# Actuators.net
KiCad netlist of a schematic drawn in Altium Designer
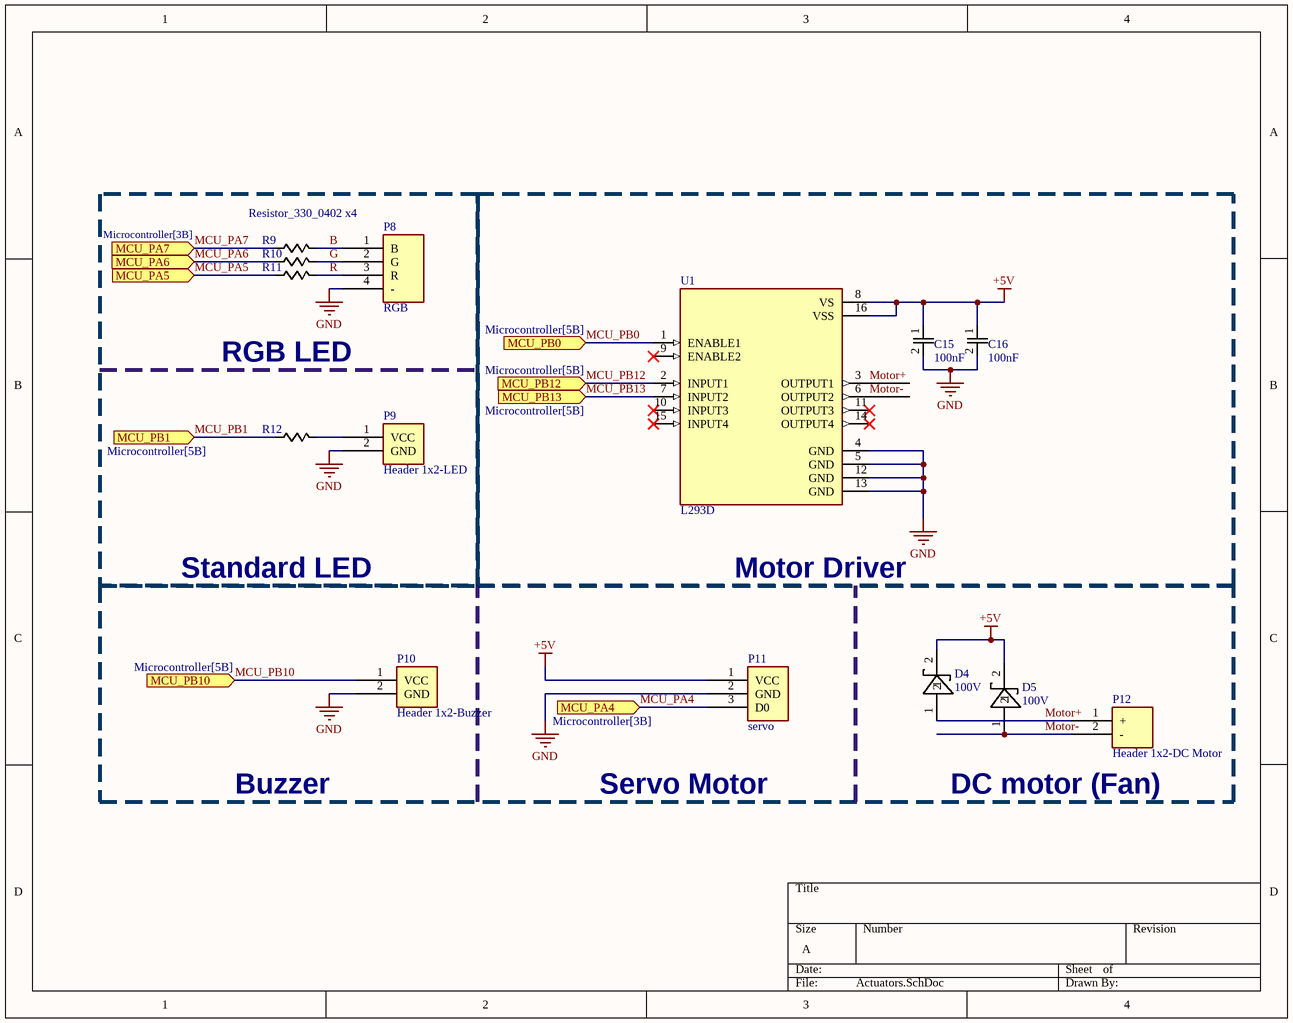
[diagram p0: Actuators.SchDoc]

(export (version "E")
  (design (tool "Eeschema 10.0.6"))
  (components
    (comp (ref "C15")
      (value "100nF")
      (footprint "CAPC1005X55N")
      (description "CAP CER 100nF 16V X7R 0402")
      (fields
        (field (name "MANUFACTURER") "Samsung Electro-Mechanics")
        (field (name "MANUFACTURER PART #") "CL05B104KO5NNNC")
      )
      (libsource (lib "Actuators") (part "Cap_100nF_0402"))
    )
    (comp (ref "C16")
      (value "100nF")
      (footprint "CAPC1005X55N")
      (description "CAP CER 100nF 16V X7R 0402")
      (fields
        (field (name "MANUFACTURER") "Samsung Electro-Mechanics")
        (field (name "MANUFACTURER PART #") "CL05B104KO5NNNC")
      )
      (libsource (lib "Actuators") (part "Cap_100nF_0402"))
    )
    (comp (ref "D4")
      (value "100V")
      (footprint "Schottky.D")
      (description "100V 850mV@5A 5A SMAG Schottky Diodes ROHS")
      (fields (field (name "MANUFACTURER") "Nexperia") (field (name "MFR. PART #") "BAT54S,215"))
      (libsource (lib "Actuators") (part "Schottky_D"))
    )
    (comp (ref "D5")
      (value "100V")
      (footprint "Schottky.D")
      (description "100V 850mV@5A 5A SMAG Schottky Diodes ROHS")
      (fields (field (name "MANUFACTURER") "Nexperia") (field (name "MFR. PART #") "BAT54S,215"))
      (libsource (lib "Actuators") (part "Schottky_D"))
    )
    (comp (ref "P8")
      (value "RGB")
      (footprint "Header 1x4 male")
      (libsource (lib "Actuators") (part "Header 1x4-RGB_LED"))
    )
    (comp (ref "P9")
      (value "Header 1x2-LED")
      (footprint "Header 1x2")
      (libsource (lib "Actuators") (part "Header 1x2-LED"))
    )
    (comp (ref "P10")
      (value "Header 1x2-Buzzer")
      (footprint "Header 1x2")
      (libsource (lib "Actuators") (part "Header 1x2-Buzzer"))
    )
    (comp (ref "P11")
      (value "servo")
      (footprint "HEADER 1x3 MALE")
      (description "servo-180-degree/")
      (libsource (lib "Actuators") (part "Header 1x3-Servo"))
    )
    (comp (ref "P12")
      (value "Header 1x2-DC Motor")
      (footprint "Header 1x2")
      (libsource (lib "Actuators") (part "Header 1x2-DC Motor"))
    )
    (comp (ref "R9")
      (value "Resistor_330_0402 x4")
      (footprint "RESC1005X40N")
      (description "RES 330Ω ±1% 62.5mW 0402")
      (fields (field (name "MANUFACTURER") "YAGEO") (field (name "MANUFACTURER PART #") "RC0402FR-07330RL"))
      (libsource (lib "Actuators") (part "Resistor_330_0402"))
    )
    (comp (ref "R10")
      (value "Resistor_330_0402")
      (footprint "RESC1005X40N")
      (description "RES 330Ω ±1% 62.5mW 0402")
      (fields (field (name "MANUFACTURER") "YAGEO") (field (name "MANUFACTURER PART #") "RC0402FR-07330RL"))
      (libsource (lib "Actuators") (part "Resistor_330_0402"))
    )
    (comp (ref "R11")
      (value "Resistor_330_0402")
      (footprint "RESC1005X40N")
      (description "RES 330Ω ±1% 62.5mW 0402")
      (fields (field (name "MANUFACTURER") "YAGEO") (field (name "MANUFACTURER PART #") "RC0402FR-07330RL"))
      (libsource (lib "Actuators") (part "Resistor_330_0402"))
    )
    (comp (ref "R12")
      (value "Resistor_330_0402")
      (footprint "RESC1005X40N")
      (description "RES 330Ω ±1% 62.5mW 0402")
      (fields (field (name "MANUFACTURER") "YAGEO") (field (name "MANUFACTURER PART #") "RC0402FR-07330RL"))
      (libsource (lib "Actuators") (part "Resistor_330_0402"))
    )
    (comp (ref "U1")
      (value "L293D")
      (footprint "DIP880W50P254L2000H510Q16")
      (description "Bipolar Motor Driver - Parallel 16-PowerDIP")
      (fields (field (name "MANUFACTURER") "ST"))
      (libsource (lib "Actuators") (part "L293D"))
    )
  )
  (nets
    (net (code "1") (name "+5V") (class "Default")
      (node (ref "C15") (pin "1") (pinfunction "1_1") (pintype "passive"))
      (node (ref "C16") (pin "1") (pinfunction "1_1") (pintype "passive"))
      (node (ref "D4") (pin "2") (pinfunction "2_2") (pintype "passive"))
      (node (ref "D5") (pin "2") (pinfunction "2_2") (pintype "passive"))
      (node (ref "P11") (pin "1") (pinfunction "VCC_1") (pintype "passive"))
      (node (ref "U1") (pin "16") (pinfunction "VSS_16") (pintype "power_in"))
      (node (ref "U1") (pin "8") (pinfunction "VS_8") (pintype "power_in"))
    )
    (net (code "2") (name "/B") (class "Default")
      (node (ref "P8") (pin "1") (pinfunction "B_1") (pintype "passive"))
      (node (ref "R9") (pin "2") (pinfunction "2_2") (pintype "passive"))
    )
    (net (code "3") (name "/G") (class "Default")
      (node (ref "P8") (pin "2") (pinfunction "G_2") (pintype "passive"))
      (node (ref "R10") (pin "2") (pinfunction "2_2") (pintype "passive"))
    )
    (net (code "4") (name "/MCU_PA4") (class "Default")
      (node (ref "P11") (pin "3") (pinfunction "D0_3") (pintype "passive"))
    )
    (net (code "5") (name "/MCU_PA5") (class "Default")
      (node (ref "R11") (pin "1") (pinfunction "1_1") (pintype "passive"))
    )
    (net (code "6") (name "/MCU_PA6") (class "Default")
      (node (ref "R10") (pin "1") (pinfunction "1_1") (pintype "passive"))
    )
    (net (code "7") (name "/MCU_PA7") (class "Default")
      (node (ref "R9") (pin "1") (pinfunction "1_1") (pintype "passive"))
    )
    (net (code "8") (name "/MCU_PB0") (class "Default")
      (node (ref "U1") (pin "1") (pinfunction "ENABLE1_1") (pintype "input"))
    )
    (net (code "9") (name "/MCU_PB1") (class "Default")
      (node (ref "R12") (pin "1") (pinfunction "1_1") (pintype "passive"))
    )
    (net (code "10") (name "/MCU_PB10") (class "Default")
      (node (ref "P10") (pin "1") (pinfunction "VCC_1") (pintype "passive"))
    )
    (net (code "11") (name "/MCU_PB12") (class "Default")
      (node (ref "U1") (pin "2") (pinfunction "INPUT1_2") (pintype "input"))
    )
    (net (code "12") (name "/MCU_PB13") (class "Default")
      (node (ref "U1") (pin "7") (pinfunction "INPUT2_7") (pintype "input"))
    )
    (net (code "13") (name "/Motor+") (class "Default")
      (node (ref "D4") (pin "1") (pinfunction "1_1") (pintype "passive"))
      (node (ref "P12") (pin "1") (pinfunction "+_1") (pintype "passive"))
      (node (ref "U1") (pin "3") (pinfunction "OUTPUT1_3") (pintype "output"))
    )
    (net (code "14") (name "/Motor-") (class "Default")
      (node (ref "D5") (pin "1") (pinfunction "1_1") (pintype "passive"))
      (node (ref "P12") (pin "2") (pinfunction "-_2") (pintype "passive"))
      (node (ref "U1") (pin "6") (pinfunction "OUTPUT2_6") (pintype "output"))
    )
    (net (code "15") (name "/R") (class "Default")
      (node (ref "P8") (pin "3") (pinfunction "R_3") (pintype "passive"))
      (node (ref "R11") (pin "2") (pinfunction "2_2") (pintype "passive"))
    )
    (net (code "16") (name "GND") (class "Default")
      (node (ref "C15") (pin "2") (pinfunction "2_2") (pintype "passive"))
      (node (ref "C16") (pin "2") (pinfunction "2_2") (pintype "passive"))
      (node (ref "P10") (pin "2") (pinfunction "GND_2") (pintype "passive"))
      (node (ref "P11") (pin "2") (pinfunction "GND_2") (pintype "passive"))
      (node (ref "P8") (pin "4") (pinfunction "-_4") (pintype "passive"))
      (node (ref "P9") (pin "2") (pinfunction "GND_2") (pintype "passive"))
      (node (ref "U1") (pin "12") (pinfunction "GND_12") (pintype "power_in"))
      (node (ref "U1") (pin "13") (pinfunction "GND_13") (pintype "power_in"))
      (node (ref "U1") (pin "4") (pinfunction "GND_4") (pintype "power_in"))
      (node (ref "U1") (pin "5") (pinfunction "GND_5") (pintype "power_in"))
    )
    (net (code "17") (name "Net-(P9-VCC)") (class "Default")
      (node (ref "P9") (pin "1") (pinfunction "VCC_1") (pintype "passive"))
      (node (ref "R12") (pin "2") (pinfunction "2_2") (pintype "passive"))
    )
    (net (code "18") (name "unconnected-(U1-ENABLE2-Pad9)") (class "Default")
      (node (ref "U1") (pin "9") (pinfunction "ENABLE2_9") (pintype "input+no_connect"))
    )
    (net (code "19") (name "unconnected-(U1-INPUT3-Pad10)") (class "Default")
      (node (ref "U1") (pin "10") (pinfunction "INPUT3_10") (pintype "input+no_connect"))
    )
    (net (code "20") (name "unconnected-(U1-INPUT4-Pad15)") (class "Default")
      (node (ref "U1") (pin "15") (pinfunction "INPUT4_15") (pintype "input+no_connect"))
    )
    (net (code "21") (name "unconnected-(U1-OUTPUT3-Pad11)") (class "Default")
      (node (ref "U1") (pin "11") (pinfunction "OUTPUT3_11") (pintype "output+no_connect"))
    )
    (net (code "22") (name "unconnected-(U1-OUTPUT4-Pad14)") (class "Default")
      (node (ref "U1") (pin "14") (pinfunction "OUTPUT4_14") (pintype "output+no_connect"))
    )
  )
)
